# LDR_Schaltplan.net
KiCad netlist of a schematic drawn in EAGLE
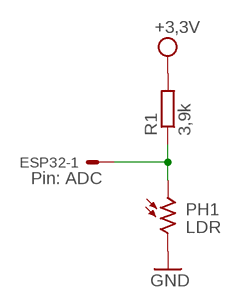
[diagram p0: schematic, sheet 1]

(export (version "E")
  (design (tool "Eeschema 10.0.6"))
  (components
    (comp (ref "ESP32")
      (value "Pin: ADC")
      (footprint "eagle-import:332-02")
      (libsource (lib "eagle-import") (part "332-02"))
    )
    (comp (ref "PH1")
      (value "LDR")
      (footprint "eagle-import:T0-46-A10XX")
      (libsource (lib "eagle-import") (part "A1050_09"))
    )
    (comp (ref "R1")
      (value "3,9k")
      (footprint "eagle-import:0207_10")
      (libsource (lib "eagle-import") (part "R-EU_0207/10"))
    )
  )
  (nets
    (net (code "1") (name "+3,3V") (class "Default")
      (node (ref "R1") (pin "2") (pinfunction "2_2") (pintype "passive"))
    )
    (net (code "2") (name "GND") (class "Default")
      (node (ref "PH1") (pin "2") (pinfunction "2_2") (pintype "passive"))
    )
    (net (code "3") (name "Net-(ESP32A-S)") (class "Default")
      (node (ref "ESP32") (pin "1") (pinfunction "S_1") (pintype "passive"))
      (node (ref "PH1") (pin "1") (pinfunction "1_1") (pintype "passive"))
      (node (ref "R1") (pin "1") (pinfunction "1_1") (pintype "passive"))
    )
  )
)
